# blink1mk2_v2d4_usbpcb.net
KiCad netlist of a schematic drawn in EAGLE
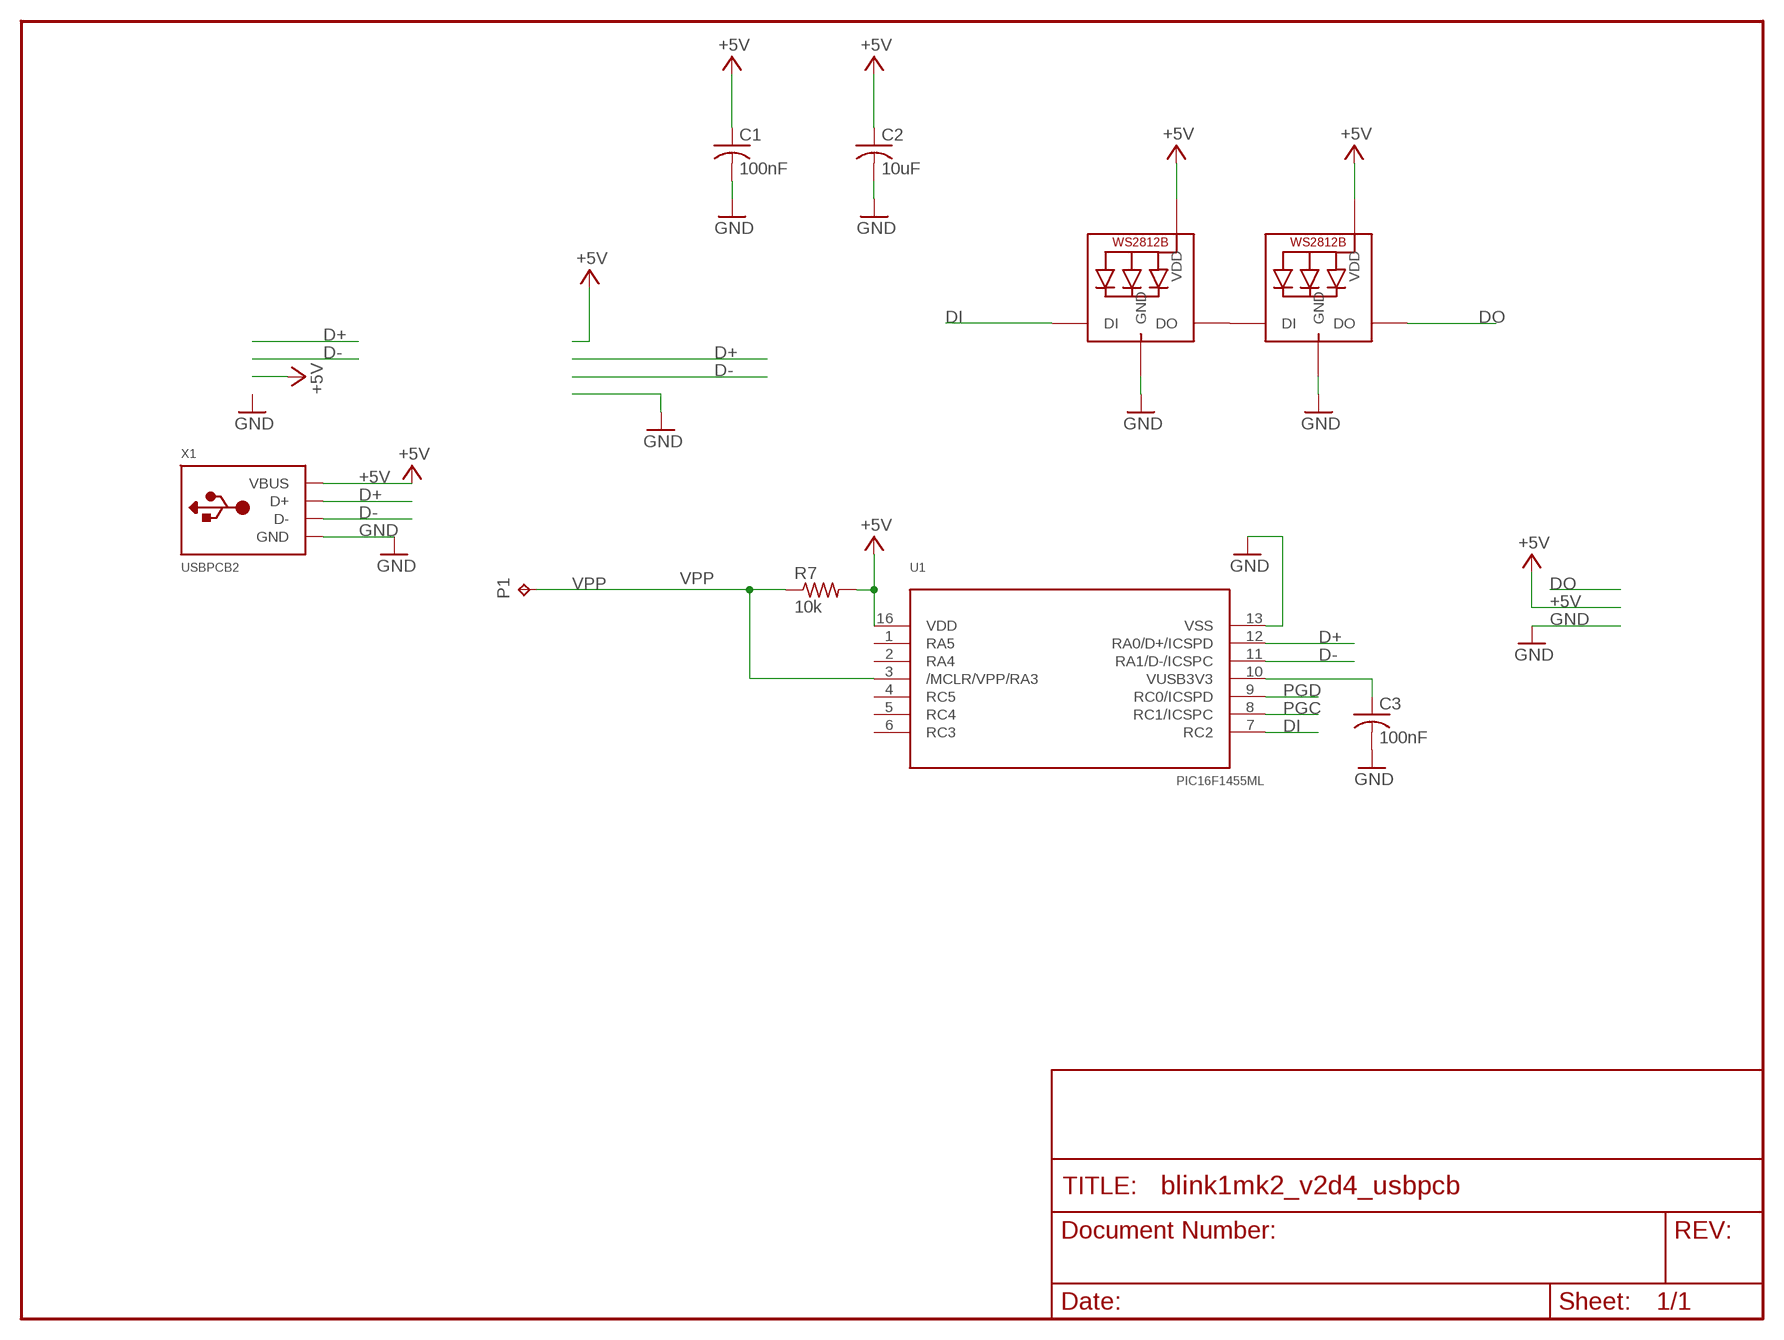
[diagram p0: schematic, sheet 1]

(export (version "E")
  (design (tool "Eeschema 10.0.6"))
  (components
    (comp (ref "C1")
      (value "100nF")
      (footprint "eagle-import:C0603")
      (libsource (lib "eagle-import") (part "C-USC0603"))
    )
    (comp (ref "C2")
      (value "10uF")
      (footprint "eagle-import:C0603")
      (libsource (lib "eagle-import") (part "C-USC0603"))
    )
    (comp (ref "C3")
      (value "100nF")
      (footprint "eagle-import:C0603")
      (libsource (lib "eagle-import") (part "C-USC0603"))
    )
    (comp (ref "LED1")
      (value "WS2812B4020SIDE")
      (footprint "eagle-import:SK6812-SIDE")
      (libsource (lib "eagle-import") (part "WS2812B4020SIDE"))
    )
    (comp (ref "LED2")
      (value "WS2812B4020SIDE")
      (footprint "eagle-import:SK6812-SIDE")
      (libsource (lib "eagle-import") (part "WS2812B4020SIDE"))
    )
    (comp (ref "P1")
      (value "TPTP11SQ")
      (footprint "eagle-import:TP11SQ")
      (libsource (lib "eagle-import") (part "TPTP11SQ"))
    )
    (comp (ref "R7")
      (value "10k")
      (footprint "eagle-import:R0603")
      (libsource (lib "eagle-import") (part "R-US_R0603"))
    )
    (comp (ref "U1")
      (value "PIC16F1455ML")
      (footprint "eagle-import:QFN16_4X4")
      (libsource (lib "eagle-import") (part "PIC16F1455ML"))
    )
    (comp (ref "X1")
      (value "USBPCB2")
      (footprint "eagle-import:USB-A-PCB-2")
      (libsource (lib "eagle-import") (part "USBPCB2"))
    )
  )
  (nets
    (net (code "1") (name "+5V") (class "Default")
      (node (ref "C1") (pin "1") (pinfunction "1_1") (pintype "passive"))
      (node (ref "C2") (pin "1") (pinfunction "1_1") (pintype "passive"))
      (node (ref "LED1") (pin "1-VDD") (pinfunction "VDD_1-VDD") (pintype "power_in"))
      (node (ref "LED2") (pin "1-VDD") (pinfunction "VDD_1-VDD") (pintype "power_in"))
      (node (ref "R7") (pin "2") (pinfunction "2_2") (pintype "passive"))
      (node (ref "U1") (pin "16") (pinfunction "VDD_16") (pintype "bidirectional"))
      (node (ref "X1") (pin "5V") (pinfunction "VBUS_5V") (pintype "power_in"))
    )
    (net (code "2") (name "/D+") (class "Default")
      (node (ref "U1") (pin "12") (pinfunction "RA0/D+/ICSPD_12") (pintype "bidirectional"))
      (node (ref "X1") (pin "USB_P") (pinfunction "D+_USB_P") (pintype "bidirectional"))
    )
    (net (code "3") (name "/D-") (class "Default")
      (node (ref "U1") (pin "11") (pinfunction "RA1/D-/ICSPC_11") (pintype "bidirectional"))
      (node (ref "X1") (pin "USB_M") (pinfunction "D-_USB_M") (pintype "bidirectional"))
    )
    (net (code "4") (name "/DI") (class "Default")
      (node (ref "LED1") (pin "4-DIN") (pinfunction "DI_4-DIN") (pintype "input"))
      (node (ref "U1") (pin "7") (pinfunction "RC2_7") (pintype "bidirectional"))
    )
    (net (code "5") (name "/DO") (class "Default")
      (node (ref "LED2") (pin "2-DOUT") (pinfunction "DO_2-DOUT") (pintype "output"))
    )
    (net (code "6") (name "/PGC") (class "Default")
      (node (ref "U1") (pin "8") (pinfunction "RC1/ICSPC_8") (pintype "bidirectional"))
    )
    (net (code "7") (name "/PGD") (class "Default")
      (node (ref "U1") (pin "9") (pinfunction "RC0/ICSPD_9") (pintype "bidirectional"))
    )
    (net (code "8") (name "/VPP") (class "Default")
      (node (ref "P1") (pin "TP") (pinfunction "TP_TP") (pintype "input"))
      (node (ref "R7") (pin "1") (pinfunction "1_1") (pintype "passive"))
      (node (ref "U1") (pin "3") (pinfunction "/MCLR/VPP/RA3_3") (pintype "bidirectional"))
    )
    (net (code "9") (name "GND") (class "Default")
      (node (ref "C1") (pin "2") (pinfunction "2_2") (pintype "passive"))
      (node (ref "C2") (pin "2") (pinfunction "2_2") (pintype "passive"))
      (node (ref "C3") (pin "2") (pinfunction "2_2") (pintype "passive"))
      (node (ref "LED1") (pin "3-GND") (pinfunction "GND_3-GND") (pintype "power_in"))
      (node (ref "LED2") (pin "3-GND") (pinfunction "GND_3-GND") (pintype "power_in"))
      (node (ref "U1") (pin "13") (pinfunction "VSS_13") (pintype "bidirectional"))
      (node (ref "X1") (pin "GND") (pinfunction "GND_GND") (pintype "power_in"))
    )
    (net (code "10") (name "Net-(LED1-DO)") (class "Default")
      (node (ref "LED1") (pin "2-DOUT") (pinfunction "DO_2-DOUT") (pintype "output"))
      (node (ref "LED2") (pin "4-DIN") (pinfunction "DI_4-DIN") (pintype "input"))
    )
    (net (code "11") (name "Net-(U1-VUSB3V3)") (class "Default")
      (node (ref "C3") (pin "1") (pinfunction "1_1") (pintype "passive"))
      (node (ref "U1") (pin "10") (pinfunction "VUSB3V3_10") (pintype "bidirectional"))
    )
    (net (code "12") (name "unconnected-(U1-RA4-Pad2)") (class "Default")
      (node (ref "U1") (pin "2") (pinfunction "RA4_2") (pintype "bidirectional"))
    )
    (net (code "13") (name "unconnected-(U1-RA5-Pad1)") (class "Default")
      (node (ref "U1") (pin "1") (pinfunction "RA5_1") (pintype "bidirectional"))
    )
    (net (code "14") (name "unconnected-(U1-RC3-Pad6)") (class "Default")
      (node (ref "U1") (pin "6") (pinfunction "RC3_6") (pintype "bidirectional"))
    )
    (net (code "15") (name "unconnected-(U1-RC4-Pad5)") (class "Default")
      (node (ref "U1") (pin "5") (pinfunction "RC4_5") (pintype "bidirectional"))
    )
    (net (code "16") (name "unconnected-(U1-RC5-Pad4)") (class "Default")
      (node (ref "U1") (pin "4") (pinfunction "RC5_4") (pintype "bidirectional"))
    )
  )
)
